# power2.net
KiCad netlist of a schematic drawn in Altium Designer
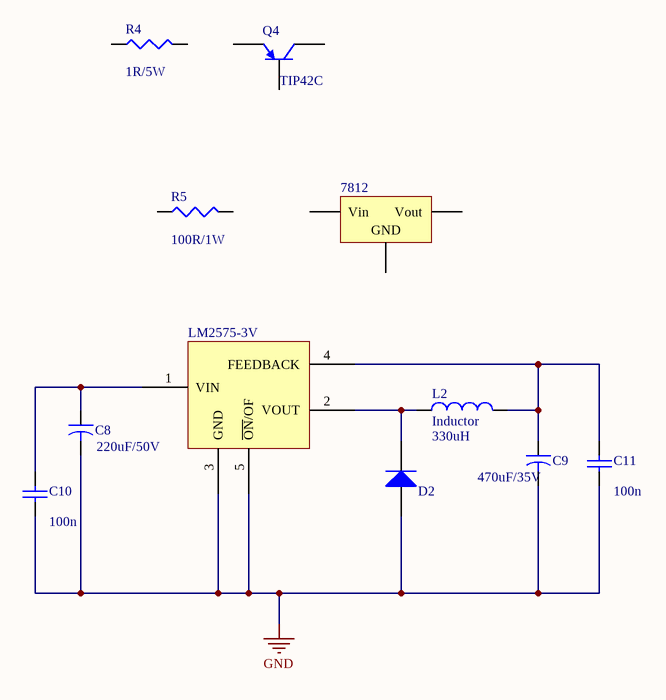
[diagram p0: power2.SchDoc]

(export (version "E")
  (design (tool "Eeschema 10.0.6"))
  (components
    (comp (ref "7812")
      (value "Volt Reg")
      (footprint "Device:78xx_NO")
      (description "Voltage Regulator")
      (fields (field (name "PUBLISHER") "Altium Limited"))
      (libsource (lib "Miscellaneous Devices") (part "Volt Reg"))
    )
    (comp (ref "C8")
      (value "220uF/50V")
      (footprint "Device:TU 220uF/50V")
      (description "Capacitor")
      (fields (field (name "Comment") "Cap2") (field (name "PUBLISHER") "Altium Limited"))
      (libsource (lib "Miscellaneous Devices") (part "Cap2"))
    )
    (comp (ref "C9")
      (value "470uF/35V")
      (footprint "Device:TU 470uF/50V")
      (description "Capacitor")
      (fields (field (name "Comment") "Cap2") (field (name "PUBLISHER") "Altium Limited"))
      (libsource (lib "Miscellaneous Devices") (part "Cap2"))
    )
    (comp (ref "C10")
      (value "100n")
      (footprint "Device:tu_gom")
      (description "Capacitor (Semiconductor SIM Model)")
      (fields (field (name "Comment") "Cap Semi") (field (name "PUBLISHER") "Altium Limited"))
      (libsource (lib "Miscellaneous Devices") (part "Cap Semi"))
    )
    (comp (ref "C11")
      (value "100n")
      (footprint "Device:tu_gom")
      (description "Capacitor (Semiconductor SIM Model)")
      (fields (field (name "Comment") "Cap Semi") (field (name "PUBLISHER") "Altium Limited"))
      (libsource (lib "Miscellaneous Devices") (part "Cap Semi"))
    )
    (comp (ref "D2")
      (value "Diode")
      (footprint "Device:D_1A")
      (libsource (lib "Device_Component") (part "Diode"))
    )
    (comp (ref "L2")
      (value "Inductor")
      (footprint "Device:R_Nor")
      (fields (field (name "ALTIUM_VALUE") "330uH") (field (name "PUBLISHER") "Altium Limited"))
      (libsource (lib "Miscellaneous Devices") (part "Inductor"))
    )
    (comp (ref "LM2575-3V")
      (value "LM2575-xx")
      (footprint "Device:LM2575_3")
      (libsource (lib "Device_Component") (part "LM2575-3V"))
    )
    (comp (ref "Q4")
      (value "TIP42C")
      (footprint "Device:TIP42C")
      (description "PNP Bipolar Transistor")
      (fields (field (name "PUBLISHER") "Altium Limited"))
      (libsource (lib "Miscellaneous Devices") (part "PNP"))
    )
    (comp (ref "R4")
      (value "1R/5W")
      (footprint "Device:R_CS1R/5W")
      (description "Resistor")
      (fields (field (name "Comment") "Res3") (field (name "PUBLISHER") "Altium Limited"))
      (libsource (lib "Miscellaneous Devices") (part "Res3"))
    )
    (comp (ref "R5")
      (value "100R/1W")
      (footprint "Device:R_Nor")
      (description "Resistor")
      (fields (field (name "Comment") "Res3") (field (name "PUBLISHER") "Altium Limited"))
      (libsource (lib "Miscellaneous Devices") (part "Res3"))
    )
  )
  (nets
    (net (code "1") (name "GND") (class "Default")
      (node (ref "C10") (pin "1") (pinfunction "1_1") (pintype "passive"))
      (node (ref "C11") (pin "1") (pinfunction "1_1") (pintype "passive"))
      (node (ref "C8") (pin "2") (pinfunction "2_2") (pintype "passive"))
      (node (ref "C9") (pin "2") (pinfunction "2_2") (pintype "passive"))
      (node (ref "D2") (pin "1") (pinfunction "A_1") (pintype "passive"))
      (node (ref "LM2575-3V") (pin "3") (pinfunction "GND_3") (pintype "passive"))
      (node (ref "LM2575-3V") (pin "5") (pinfunction "~{ON}/OF_5") (pintype "passive"))
    )
    (net (code "2") (name "Net-(D2-K)") (class "Default")
      (node (ref "D2") (pin "2") (pinfunction "K_2") (pintype "passive"))
      (node (ref "L2") (pin "1") (pinfunction "1_1") (pintype "passive"))
      (node (ref "LM2575-3V") (pin "2") (pinfunction "VOUT_2") (pintype "passive"))
    )
    (net (code "3") (name "Net-(LM2575-3V-FEEDBACK)") (class "Default")
      (node (ref "C11") (pin "2") (pinfunction "2_2") (pintype "passive"))
      (node (ref "C9") (pin "1") (pinfunction "1_1") (pintype "passive"))
      (node (ref "L2") (pin "2") (pinfunction "2_2") (pintype "passive"))
      (node (ref "LM2575-3V") (pin "4") (pinfunction "FEEDBACK_4") (pintype "passive"))
    )
    (net (code "4") (name "Net-(LM2575-3V-VIN)") (class "Default")
      (node (ref "C10") (pin "2") (pinfunction "2_2") (pintype "passive"))
      (node (ref "C8") (pin "1") (pinfunction "1_1") (pintype "passive"))
      (node (ref "LM2575-3V") (pin "1") (pinfunction "VIN_1") (pintype "passive"))
    )
    (net (code "5") (name "unconnected-(7812-GND-Pad2)") (class "Default")
      (node (ref "7812") (pin "2") (pinfunction "GND_2") (pintype "passive"))
    )
    (net (code "6") (name "unconnected-(7812-Vin-Pad1)") (class "Default")
      (node (ref "7812") (pin "1") (pinfunction "Vin_1") (pintype "passive"))
    )
    (net (code "7") (name "unconnected-(7812-Vout-Pad3)") (class "Default")
      (node (ref "7812") (pin "3") (pinfunction "Vout_3") (pintype "passive"))
    )
    (net (code "8") (name "unconnected-(Q4-B-Pad1)") (class "Default")
      (node (ref "Q4") (pin "1") (pinfunction "B_1") (pintype "passive"))
    )
    (net (code "9") (name "unconnected-(Q4-C-Pad2)") (class "Default")
      (node (ref "Q4") (pin "2") (pinfunction "C_2") (pintype "passive"))
    )
    (net (code "10") (name "unconnected-(Q4-E-Pad3)") (class "Default")
      (node (ref "Q4") (pin "3") (pinfunction "E_3") (pintype "passive"))
    )
    (net (code "11") (name "unconnected-(R4-Pad1)") (class "Default")
      (node (ref "R4") (pin "1") (pinfunction "1_1") (pintype "passive"))
    )
    (net (code "12") (name "unconnected-(R4-Pad2)") (class "Default")
      (node (ref "R4") (pin "2") (pinfunction "2_2") (pintype "passive"))
    )
    (net (code "13") (name "unconnected-(R5-Pad1)") (class "Default")
      (node (ref "R5") (pin "1") (pinfunction "1_1") (pintype "passive"))
    )
    (net (code "14") (name "unconnected-(R5-Pad2)") (class "Default")
      (node (ref "R5") (pin "2") (pinfunction "2_2") (pintype "passive"))
    )
  )
)
